# -_-V2.net
KiCad netlist of a schematic drawn in Altium Designer
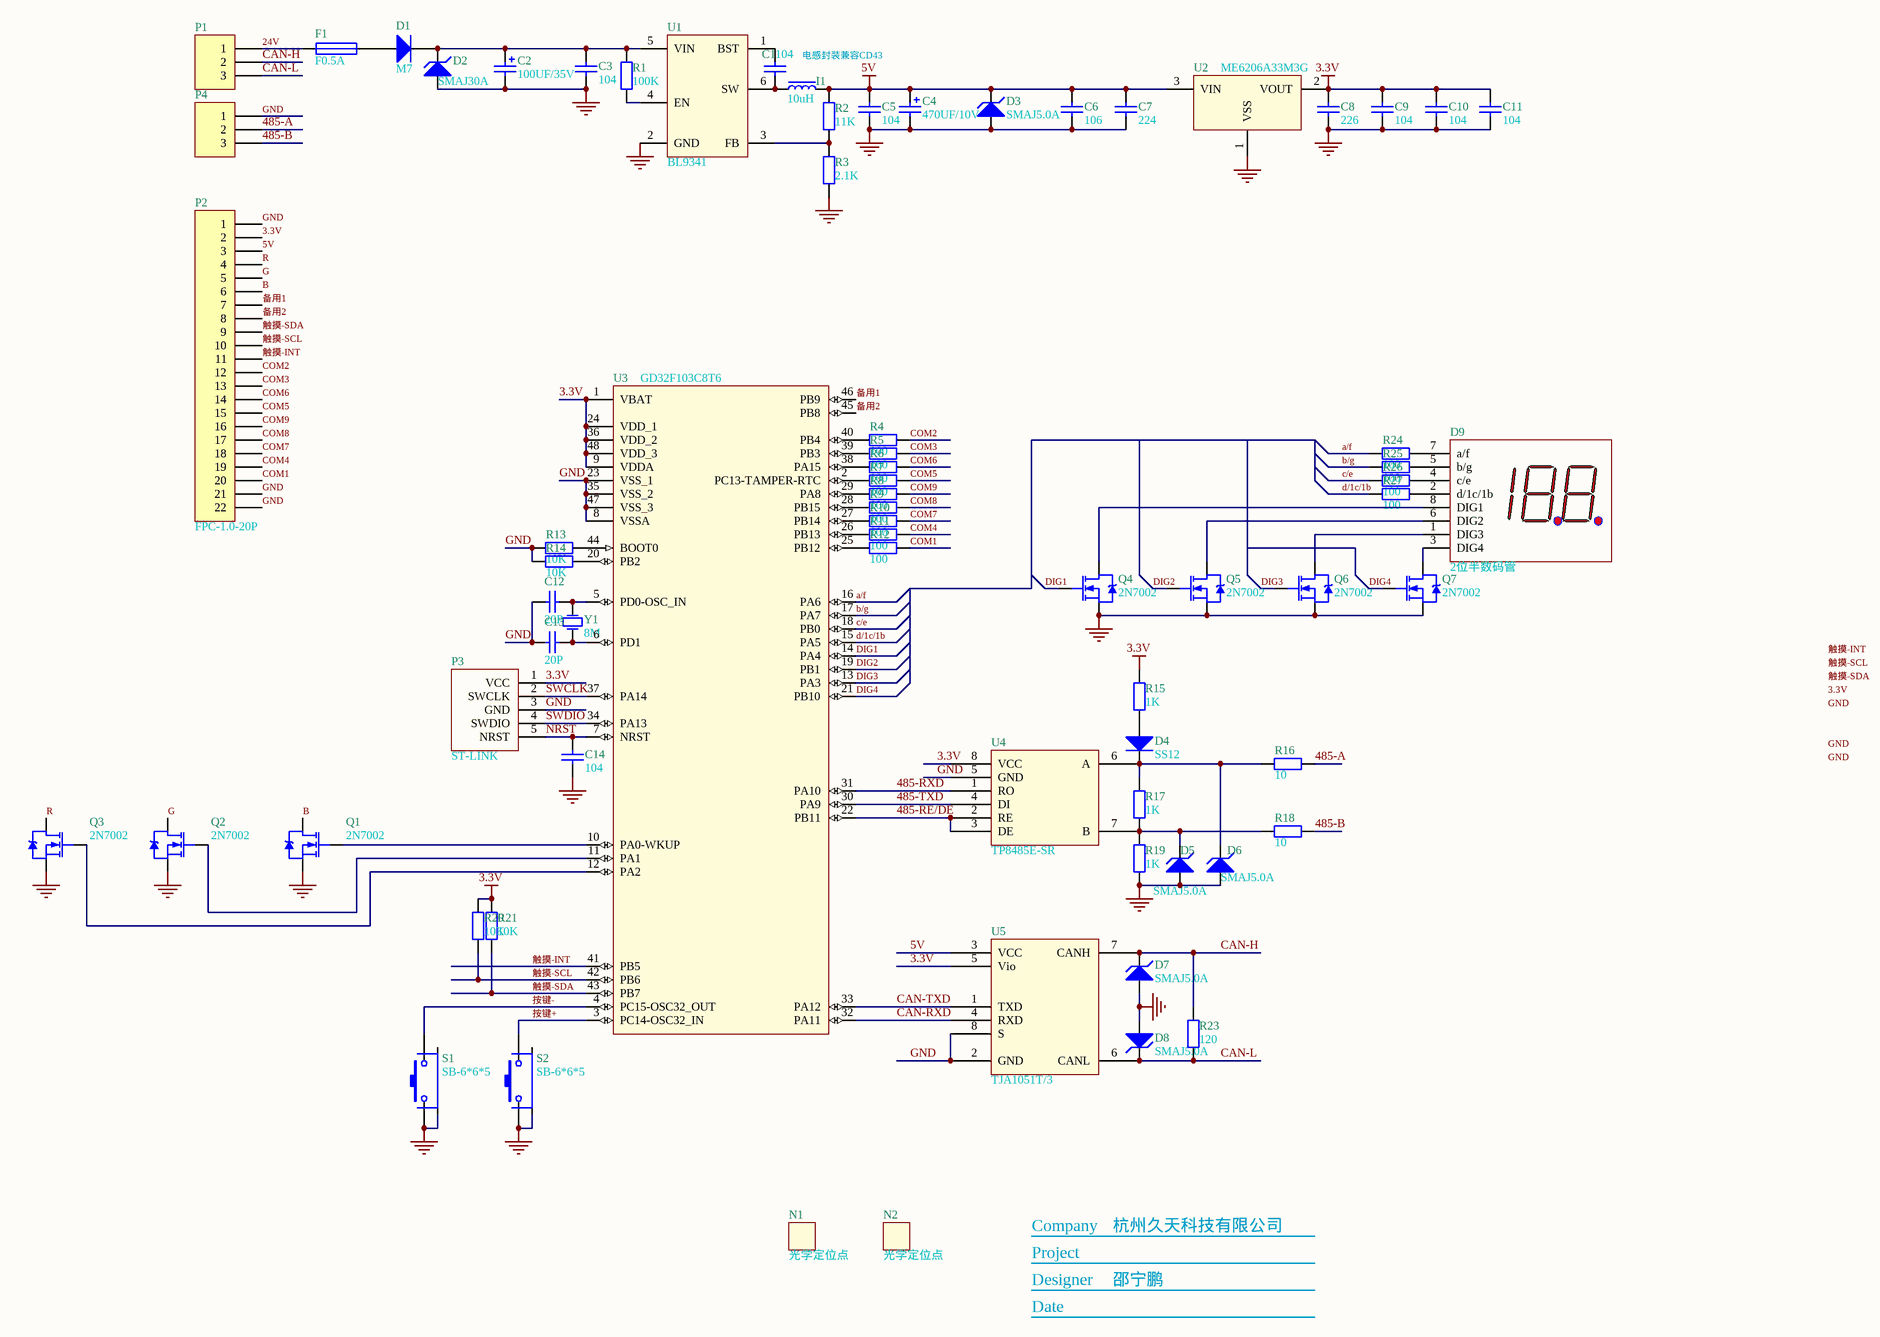
[diagram p0: 九键触摸面板-控制板-V2.SchDoc]

(export (version "E")
  (design (tool "Eeschema 10.0.6"))
  (components
    (comp (ref "C1")
      (value "104")
      (footprint "C-0603")
      (description "Capacitor")
      (fields (field (name "PUBLISHER") "Altium Limited"))
      (libsource (lib "元件2.0") (part "Cap"))
    )
    (comp (ref "C2")
      (value "100UF/35V")
      (footprint "贴片固态电容6.3*7.7")
      (description "Polarized Capacitor (Radial)")
      (fields (field (name "PUBLISHER") "Altium Limited"))
      (libsource (lib "元件2.0") (part "Cap Pol1"))
    )
    (comp (ref "C3")
      (value "104")
      (footprint "C-0603")
      (description "Capacitor")
      (fields (field (name "PUBLISHER") "Altium Limited"))
      (libsource (lib "元件2.0") (part "Cap"))
    )
    (comp (ref "C4")
      (value "470UF/10V")
      (footprint "贴片固态电容6.3*7.7")
      (description "Polarized Capacitor (Radial)")
      (fields (field (name "PUBLISHER") "Altium Limited"))
      (libsource (lib "元件2.0") (part "Cap Pol1"))
    )
    (comp (ref "C5")
      (value "104")
      (footprint "C-0603")
      (description "Capacitor")
      (fields (field (name "PUBLISHER") "Altium Limited"))
      (libsource (lib "元件2.0") (part "Cap"))
    )
    (comp (ref "C6")
      (value "106")
      (footprint "C-0603")
      (description "Capacitor")
      (fields (field (name "PUBLISHER") "Altium Limited"))
      (libsource (lib "元件2.0") (part "Cap"))
    )
    (comp (ref "C7")
      (value "224")
      (footprint "C-0603")
      (description "Capacitor")
      (fields (field (name "PUBLISHER") "Altium Limited"))
      (libsource (lib "元件2.0") (part "Cap"))
    )
    (comp (ref "C8")
      (value "226")
      (footprint "C-0603")
      (description "Capacitor")
      (fields (field (name "PUBLISHER") "Altium Limited"))
      (libsource (lib "元件2.0") (part "Cap"))
    )
    (comp (ref "C9")
      (value "104")
      (footprint "C-0603")
      (description "Capacitor")
      (fields (field (name "PUBLISHER") "Altium Limited"))
      (libsource (lib "元件2.0") (part "Cap"))
    )
    (comp (ref "C10")
      (value "104")
      (footprint "C-0603")
      (description "Capacitor")
      (fields (field (name "PUBLISHER") "Altium Limited"))
      (libsource (lib "元件2.0") (part "Cap"))
    )
    (comp (ref "C11")
      (value "104")
      (footprint "C-0603")
      (description "Capacitor")
      (fields (field (name "PUBLISHER") "Altium Limited"))
      (libsource (lib "元件2.0") (part "Cap"))
    )
    (comp (ref "C12")
      (value "20P")
      (footprint "C-0603")
      (description "0805")
      (fields (field (name "PUBLISHER") "Altium Limited"))
      (libsource (lib "2电容-V1.0") (part "Cap-0603"))
    )
    (comp (ref "C13")
      (value "20P")
      (footprint "C-0603")
      (description "0805")
      (fields (field (name "PUBLISHER") "Altium Limited"))
      (libsource (lib "2电容-V1.0") (part "Cap-0603"))
    )
    (comp (ref "C14")
      (value "104")
      (footprint "C-0603")
      (description "0805")
      (fields (field (name "PUBLISHER") "Altium Limited"))
      (libsource (lib "2电容-V1.0") (part "Cap-0603"))
    )
    (comp (ref "D1")
      (value "M7")
      (footprint "SMA")
      (description "SMA")
      (fields (field (name "PUBLISHER") "Altium Limited"))
      (libsource (lib "4二极管-V1.1") (part "M7"))
    )
    (comp (ref "D2")
      (value "SMAJ30A")
      (footprint "SMA")
      (description "SMB")
      (libsource (lib "4二极管-V1.1") (part "TVS-1"))
    )
    (comp (ref "D3")
      (value "SMAJ5.0A")
      (footprint "SMA")
      (description "SMB")
      (libsource (lib "4二极管-V1.1") (part "TVS-1"))
    )
    (comp (ref "D4")
      (value "SS12")
      (footprint "SOD-323/0805")
      (description "SMA")
      (libsource (lib "4二极管-V1.1") (part "SS14"))
    )
    (comp (ref "D5")
      (value "SMAJ5.0A")
      (footprint "SMA")
      (description "SMB")
      (libsource (lib "4二极管-V1.1") (part "TVS-1"))
    )
    (comp (ref "D6")
      (value "SMAJ5.0A")
      (footprint "SMA")
      (description "SMB")
      (libsource (lib "4二极管-V1.1") (part "TVS-1"))
    )
    (comp (ref "D7")
      (value "SMAJ5.0A")
      (footprint "SMA")
      (description "SMB")
      (libsource (lib "4二极管-V1.1") (part "TVS-1"))
    )
    (comp (ref "D8")
      (value "SMAJ5.0A")
      (footprint "SMA")
      (description "SMB")
      (libsource (lib "4二极管-V1.1") (part "TVS-1"))
    )
    (comp (ref "D9") (value "2位半数码管") (footprint "2位半0.25英寸") (libsource (lib "7显示屏-V1.0") (part "2位半数码管")))
    (comp (ref "F1")
      (value "F0.5A")
      (footprint "FUSE-3*10带引线")
      (description "Fuse")
      (fields (field (name "PUBLISHER") "Altium Limited"))
      (libsource (lib "11其他元件-V1.0") (part "Fuse 1"))
    )
    (comp (ref "I1") (value "10uH") (footprint "4030") (libsource (lib "3电感-V1.0") (part "Inductance3")))
    (comp (ref "N1") (value "光学定位点") (footprint "MARK-1mm-3mm") (libsource (lib "11其他元件-V1.0") (part "无引脚")))
    (comp (ref "N2") (value "光学定位点") (footprint "MARK-1mm-3mm") (libsource (lib "11其他元件-V1.0") (part "无引脚")))
    (comp (ref "P1")
      (value "~")
      (footprint "KF128-3P")
      (description "Header, 3-Pin")
      (fields (field (name "PUBLISHER") "Altium Limited"))
      (libsource (lib "5排针-V1.0") (part "Header 3"))
    )
    (comp (ref "P2")
      (value "FPC-1.0-20P")
      (footprint "FPC-1.0mm_20P下接翻盖")
      (description "Header, 22-Pin")
      (fields (field (name "PUBLISHER") "Altium Limited"))
      (libsource (lib "5排针-V1.0") (part "Header 22"))
    )
    (comp (ref "P3") (value "ST-LINK") (footprint "5P下载口") (libsource (lib "下载口") (part "ST-LINK-STM32")))
    (comp (ref "P4")
      (value "~")
      (footprint "KF128-3P")
      (description "Header, 3-Pin")
      (fields (field (name "PUBLISHER") "Altium Limited"))
      (libsource (lib "5排针-V1.0") (part "Header 3"))
    )
    (comp (ref "Q1") (value "2N7002") (footprint "SOT-23") (libsource (lib "4二极管-V1.1") (part "2N7002")))
    (comp (ref "Q2") (value "2N7002") (footprint "SOT-23") (libsource (lib "4二极管-V1.1") (part "2N7002")))
    (comp (ref "Q3") (value "2N7002") (footprint "SOT-23") (libsource (lib "4二极管-V1.1") (part "2N7002")))
    (comp (ref "Q4") (value "2N7002") (footprint "SOT-23") (libsource (lib "4二极管-V1.1") (part "2N7002")))
    (comp (ref "Q5") (value "2N7002") (footprint "SOT-23") (libsource (lib "4二极管-V1.1") (part "2N7002")))
    (comp (ref "Q6") (value "2N7002") (footprint "SOT-23") (libsource (lib "4二极管-V1.1") (part "2N7002")))
    (comp (ref "Q7") (value "2N7002") (footprint "SOT-23") (libsource (lib "4二极管-V1.1") (part "2N7002")))
    (comp (ref "R1")
      (value "100K")
      (footprint "R-0603")
      (description "0603")
      (fields (field (name "PUBLISHER") "Altium Limited"))
      (libsource (lib "1电阻-V1.0") (part "Res2-0603"))
    )
    (comp (ref "R2")
      (value "11K")
      (footprint "R-0603")
      (description "0603")
      (fields (field (name "PUBLISHER") "Altium Limited"))
      (libsource (lib "1电阻-V1.0") (part "Res2-0603"))
    )
    (comp (ref "R3")
      (value "2.1K")
      (footprint "R-0603")
      (description "0603")
      (fields (field (name "PUBLISHER") "Altium Limited"))
      (libsource (lib "1电阻-V1.0") (part "Res2-0603"))
    )
    (comp (ref "R4")
      (value "100")
      (footprint "R-0603")
      (description "0603")
      (fields (field (name "PUBLISHER") "Altium Limited"))
      (libsource (lib "") (part "Res2-0603_1"))
    )
    (comp (ref "R5")
      (value "100")
      (footprint "R-0603")
      (description "0603")
      (fields (field (name "PUBLISHER") "Altium Limited"))
      (libsource (lib "") (part "Res2-0603_1"))
    )
    (comp (ref "R6")
      (value "100")
      (footprint "R-0603")
      (description "0603")
      (fields (field (name "PUBLISHER") "Altium Limited"))
      (libsource (lib "") (part "Res2-0603_1"))
    )
    (comp (ref "R7")
      (value "100")
      (footprint "R-0603")
      (description "0603")
      (fields (field (name "PUBLISHER") "Altium Limited"))
      (libsource (lib "") (part "Res2-0603_1"))
    )
    (comp (ref "R8")
      (value "100")
      (footprint "R-0603")
      (description "0603")
      (fields (field (name "PUBLISHER") "Altium Limited"))
      (libsource (lib "") (part "Res2-0603_1"))
    )
    (comp (ref "R9")
      (value "100")
      (footprint "R-0603")
      (description "0603")
      (fields (field (name "PUBLISHER") "Altium Limited"))
      (libsource (lib "") (part "Res2-0603_1"))
    )
    (comp (ref "R10")
      (value "100")
      (footprint "R-0603")
      (description "0603")
      (fields (field (name "PUBLISHER") "Altium Limited"))
      (libsource (lib "") (part "Res2-0603_1"))
    )
    (comp (ref "R11")
      (value "100")
      (footprint "R-0603")
      (description "0603")
      (fields (field (name "PUBLISHER") "Altium Limited"))
      (libsource (lib "") (part "Res2-0603_1"))
    )
    (comp (ref "R12")
      (value "100")
      (footprint "R-0603")
      (description "0603")
      (fields (field (name "PUBLISHER") "Altium Limited"))
      (libsource (lib "") (part "Res2-0603_1"))
    )
    (comp (ref "R13")
      (value "10K")
      (footprint "R-0603")
      (description "0603")
      (fields (field (name "PUBLISHER") "Altium Limited"))
      (libsource (lib "1电阻-V1.0") (part "Res2-0603"))
    )
    (comp (ref "R14")
      (value "10K")
      (footprint "R-0603")
      (description "0603")
      (fields (field (name "PUBLISHER") "Altium Limited"))
      (libsource (lib "1电阻-V1.0") (part "Res2-0603"))
    )
    (comp (ref "R15")
      (value "1K")
      (footprint "R-0603")
      (description "Resistor")
      (fields (field (name "PUBLISHER") "Altium Limited"))
      (libsource (lib "元件2.0") (part "Res2"))
    )
    (comp (ref "R16")
      (value "10")
      (footprint "R-0603")
      (description "Resistor")
      (fields (field (name "PUBLISHER") "Altium Limited"))
      (libsource (lib "Miscellaneous Devices") (part "Res2"))
    )
    (comp (ref "R17")
      (value "1K")
      (footprint "R-1206")
      (description "Resistor")
      (fields (field (name "PUBLISHER") "Altium Limited"))
      (libsource (lib "") (part "Res2_1"))
    )
    (comp (ref "R18")
      (value "10")
      (footprint "R-0603")
      (description "Resistor")
      (fields (field (name "PUBLISHER") "Altium Limited"))
      (libsource (lib "Miscellaneous Devices") (part "Res2"))
    )
    (comp (ref "R19")
      (value "1K")
      (footprint "R-0603")
      (description "Resistor")
      (fields (field (name "PUBLISHER") "Altium Limited"))
      (libsource (lib "") (part "Res2_1"))
    )
    (comp (ref "R20")
      (value "10K")
      (footprint "R-0603")
      (description "0603")
      (fields (field (name "PUBLISHER") "Altium Limited"))
      (libsource (lib "") (part "Res2-0603_1"))
    )
    (comp (ref "R21")
      (value "10K")
      (footprint "R-0603")
      (description "0603")
      (fields (field (name "PUBLISHER") "Altium Limited"))
      (libsource (lib "") (part "Res2-0603_1"))
    )
    (comp (ref "R23")
      (value "120")
      (footprint "R-1206")
      (description "Resistor")
      (fields (field (name "PUBLISHER") "Altium Limited"))
      (libsource (lib "") (part "Res2_1"))
    )
    (comp (ref "R24")
      (value "100")
      (footprint "R-0603")
      (description "0603")
      (fields (field (name "PUBLISHER") "Altium Limited"))
      (libsource (lib "") (part "Res2-0603_1"))
    )
    (comp (ref "R25")
      (value "100")
      (footprint "R-0603")
      (description "0603")
      (fields (field (name "PUBLISHER") "Altium Limited"))
      (libsource (lib "") (part "Res2-0603_1"))
    )
    (comp (ref "R26")
      (value "100")
      (footprint "R-0603")
      (description "0603")
      (fields (field (name "PUBLISHER") "Altium Limited"))
      (libsource (lib "") (part "Res2-0603_1"))
    )
    (comp (ref "R27")
      (value "100")
      (footprint "R-0603")
      (description "0603")
      (fields (field (name "PUBLISHER") "Altium Limited"))
      (libsource (lib "") (part "Res2-0603_1"))
    )
    (comp (ref "S1")
      (value "SB-6*6*5")
      (footprint "SB-3*6*3.5")
      (fields (field (name "PUBLISHER") "Altium Limited"))
      (libsource (lib "开关-V1") (part "SB-6*6*5"))
    )
    (comp (ref "S2")
      (value "SB-6*6*5")
      (footprint "SB-3*6*3.5")
      (fields (field (name "PUBLISHER") "Altium Limited"))
      (libsource (lib "开关-V1") (part "SB-6*6*5"))
    )
    (comp (ref "U1") (value "BL9341") (footprint "SOT-23-6-m") (libsource (lib "电源芯片DC-DC") (part "BL9341")))
    (comp (ref "U2")
      (value "ME6206A33M3G")
      (footprint "SOT-23")
      (description "LDO稳压 SOT-23")
      (libsource (lib "电源芯片-线性稳压-V1") (part "ME6206A33M3G"))
    )
    (comp (ref "U3")
      (value "GD32F103C8T6")
      (footprint "LQFP48-L")
      (libsource (lib "9单片机-V1.0") (part "GD32F103C8T6"))
    )
    (comp (ref "U4")
      (value "TP8485E-SR")
      (footprint "SOP-8-m")
      (description "RS485总线转串口")
      (libsource (lib "集成电路1.0") (part "MAX3082"))
    )
    (comp (ref "U5") (value "TJA1051T/3") (footprint "SOP-8-M") (libsource (lib "通讯-V1") (part "TJA1051T/3")))
    (comp (ref "Y1") (value "8M") (footprint "HC-49SMD") (libsource (lib "11其他元件-V1.0") (part "晶振")))
  )
  (nets
    (net (code "1") (name "/24V") (class "Default")
      (node (ref "F1") (pin "1") (pinfunction "1_1") (pintype "passive"))
      (node (ref "P1") (pin "1") (pinfunction "1_1") (pintype "passive"))
    )
    (net (code "2") (name "/485-A") (class "Default")
      (node (ref "P4") (pin "2") (pinfunction "2_2") (pintype "passive"))
      (node (ref "R16") (pin "1") (pinfunction "1_1") (pintype "passive"))
    )
    (net (code "3") (name "/485-B") (class "Default")
      (node (ref "P4") (pin "3") (pinfunction "3_3") (pintype "passive"))
      (node (ref "R18") (pin "1") (pinfunction "1_1") (pintype "passive"))
    )
    (net (code "4") (name "/485-RE{slash}DE") (class "Default")
      (node (ref "U3") (pin "22") (pinfunction "PB11_22") (pintype "bidirectional"))
      (node (ref "U4") (pin "2") (pinfunction "RE_2") (pintype "passive"))
      (node (ref "U4") (pin "3") (pinfunction "DE_3") (pintype "passive"))
    )
    (net (code "5") (name "/485-RXD") (class "Default")
      (node (ref "U3") (pin "31") (pinfunction "PA10_31") (pintype "bidirectional"))
      (node (ref "U4") (pin "1") (pinfunction "RO_1") (pintype "passive"))
    )
    (net (code "6") (name "/485-TXD") (class "Default")
      (node (ref "U3") (pin "30") (pinfunction "PA9_30") (pintype "bidirectional"))
      (node (ref "U4") (pin "4") (pinfunction "DI_4") (pintype "passive"))
    )
    (net (code "7") (name "/B") (class "Default")
      (node (ref "P2") (pin "6") (pinfunction "6_6") (pintype "passive"))
      (node (ref "Q1") (pin "3") (pinfunction "D_3") (pintype "passive"))
    )
    (net (code "8") (name "/CAN-H") (class "Default")
      (node (ref "D7") (pin "2") (pinfunction "K_2") (pintype "passive"))
      (node (ref "P1") (pin "2") (pinfunction "2_2") (pintype "passive"))
      (node (ref "R23") (pin "1") (pinfunction "1_1") (pintype "passive"))
      (node (ref "U5") (pin "7") (pinfunction "CANH_7") (pintype "passive"))
    )
    (net (code "9") (name "/CAN-L") (class "Default")
      (node (ref "D8") (pin "2") (pinfunction "K_2") (pintype "passive"))
      (node (ref "P1") (pin "3") (pinfunction "3_3") (pintype "passive"))
      (node (ref "R23") (pin "2") (pinfunction "2_2") (pintype "passive"))
      (node (ref "U5") (pin "6") (pinfunction "CANL_6") (pintype "passive"))
    )
    (net (code "10") (name "/CAN-RXD") (class "Default")
      (node (ref "U3") (pin "32") (pinfunction "PA11_32") (pintype "bidirectional"))
      (node (ref "U5") (pin "4") (pinfunction "RXD_4") (pintype "passive"))
    )
    (net (code "11") (name "/CAN-TXD") (class "Default")
      (node (ref "U3") (pin "33") (pinfunction "PA12_33") (pintype "bidirectional"))
      (node (ref "U5") (pin "1") (pinfunction "TXD_1") (pintype "passive"))
    )
    (net (code "12") (name "/COM1") (class "Default")
      (node (ref "P2") (pin "20") (pinfunction "20_20") (pintype "passive"))
      (node (ref "R12") (pin "2") (pinfunction "2_2") (pintype "passive"))
    )
    (net (code "13") (name "/COM2") (class "Default")
      (node (ref "P2") (pin "12") (pinfunction "12_12") (pintype "passive"))
      (node (ref "R4") (pin "2") (pinfunction "2_2") (pintype "passive"))
    )
    (net (code "14") (name "/COM3") (class "Default")
      (node (ref "P2") (pin "13") (pinfunction "13_13") (pintype "passive"))
      (node (ref "R5") (pin "2") (pinfunction "2_2") (pintype "passive"))
    )
    (net (code "15") (name "/COM4") (class "Default")
      (node (ref "P2") (pin "19") (pinfunction "19_19") (pintype "passive"))
      (node (ref "R11") (pin "2") (pinfunction "2_2") (pintype "passive"))
    )
    (net (code "16") (name "/COM5") (class "Default")
      (node (ref "P2") (pin "15") (pinfunction "15_15") (pintype "passive"))
      (node (ref "R7") (pin "2") (pinfunction "2_2") (pintype "passive"))
    )
    (net (code "17") (name "/COM6") (class "Default")
      (node (ref "P2") (pin "14") (pinfunction "14_14") (pintype "passive"))
      (node (ref "R6") (pin "2") (pinfunction "2_2") (pintype "passive"))
    )
    (net (code "18") (name "/COM7") (class "Default")
      (node (ref "P2") (pin "18") (pinfunction "18_18") (pintype "passive"))
      (node (ref "R10") (pin "2") (pinfunction "2_2") (pintype "passive"))
    )
    (net (code "19") (name "/COM8") (class "Default")
      (node (ref "P2") (pin "17") (pinfunction "17_17") (pintype "passive"))
      (node (ref "R9") (pin "2") (pinfunction "2_2") (pintype "passive"))
    )
    (net (code "20") (name "/COM9") (class "Default")
      (node (ref "P2") (pin "16") (pinfunction "16_16") (pintype "passive"))
      (node (ref "R8") (pin "2") (pinfunction "2_2") (pintype "passive"))
    )
    (net (code "21") (name "/DIG1") (class "Default")
      (node (ref "Q4") (pin "1") (pinfunction "G_1") (pintype "passive"))
      (node (ref "U3") (pin "14") (pinfunction "PA4_14") (pintype "bidirectional"))
    )
    (net (code "22") (name "/DIG2") (class "Default")
      (node (ref "Q5") (pin "1") (pinfunction "G_1") (pintype "passive"))
      (node (ref "U3") (pin "19") (pinfunction "PB1_19") (pintype "bidirectional"))
    )
    (net (code "23") (name "/DIG3") (class "Default")
      (node (ref "Q6") (pin "1") (pinfunction "G_1") (pintype "passive"))
      (node (ref "U3") (pin "13") (pinfunction "PA3_13") (pintype "bidirectional"))
    )
    (net (code "24") (name "/DIG4") (class "Default")
      (node (ref "Q7") (pin "1") (pinfunction "G_1") (pintype "passive"))
      (node (ref "U3") (pin "21") (pinfunction "PB10_21") (pintype "bidirectional"))
    )
    (net (code "25") (name "/G") (class "Default")
      (node (ref "P2") (pin "5") (pinfunction "5_5") (pintype "passive"))
      (node (ref "Q2") (pin "3") (pinfunction "D_3") (pintype "passive"))
    )
    (net (code "26") (name "/NRST") (class "Default")
      (node (ref "C14") (pin "2") (pinfunction "2_2") (pintype "passive"))
      (node (ref "P3") (pin "5") (pinfunction "NRST_5") (pintype "passive"))
      (node (ref "U3") (pin "7") (pinfunction "NRST_7") (pintype "bidirectional"))
    )
    (net (code "27") (name "/R") (class "Default")
      (node (ref "P2") (pin "4") (pinfunction "4_4") (pintype "passive"))
      (node (ref "Q3") (pin "3") (pinfunction "D_3") (pintype "passive"))
    )
    (net (code "28") (name "/SWCLK") (class "Default")
      (node (ref "P3") (pin "2") (pinfunction "SWCLK_2") (pintype "passive"))
      (node (ref "U3") (pin "37") (pinfunction "PA14_37") (pintype "bidirectional"))
    )
    (net (code "29") (name "/SWDIO") (class "Default")
      (node (ref "P3") (pin "4") (pinfunction "SWDIO_4") (pintype "passive"))
      (node (ref "U3") (pin "34") (pinfunction "PA13_34") (pintype "bidirectional"))
    )
    (net (code "30") (name "/a{slash}f") (class "Default")
      (node (ref "R24") (pin "1") (pinfunction "1_1") (pintype "passive"))
      (node (ref "U3") (pin "16") (pinfunction "PA6_16") (pintype "bidirectional"))
    )
    (net (code "31") (name "/b{slash}g") (class "Default")
      (node (ref "R25") (pin "1") (pinfunction "1_1") (pintype "passive"))
      (node (ref "U3") (pin "17") (pinfunction "PA7_17") (pintype "bidirectional"))
    )
    (net (code "32") (name "/c{slash}e") (class "Default")
      (node (ref "R26") (pin "1") (pinfunction "1_1") (pintype "passive"))
      (node (ref "U3") (pin "18") (pinfunction "PB0_18") (pintype "bidirectional"))
    )
    (net (code "33") (name "/d{slash}1c{slash}1b") (class "Default")
      (node (ref "R27") (pin "1") (pinfunction "1_1") (pintype "passive"))
      (node (ref "U3") (pin "15") (pinfunction "PA5_15") (pintype "bidirectional"))
    )
    (net (code "34") (name "/备用1") (class "Default")
      (node (ref "P2") (pin "7") (pinfunction "7_7") (pintype "passive"))
      (node (ref "U3") (pin "46") (pinfunction "PB9_46") (pintype "bidirectional"))
    )
    (net (code "35") (name "/备用2") (class "Default")
      (node (ref "P2") (pin "8") (pinfunction "8_8") (pintype "passive"))
      (node (ref "U3") (pin "45") (pinfunction "PB8_45") (pintype "bidirectional"))
    )
    (net (code "36") (name "/按键+") (class "Default")
      (node (ref "S2") (pin "1") (pinfunction "1_1") (pintype "passive"))
      (node (ref "U3") (pin "3") (pinfunction "PC14-OSC32_IN_3") (pintype "bidirectional"))
    )
    (net (code "37") (name "/按键-") (class "Default")
      (node (ref "S1") (pin "1") (pinfunction "1_1") (pintype "passive"))
      (node (ref "U3") (pin "4") (pinfunction "PC15-OSC32_OUT_4") (pintype "bidirectional"))
    )
    (net (code "38") (name "/触摸-INT") (class "Default")
      (node (ref "P2") (pin "11") (pinfunction "11_11") (pintype "passive"))
      (node (ref "U3") (pin "41") (pinfunction "PB5_41") (pintype "bidirectional"))
    )
    (net (code "39") (name "/触摸-SCL") (class "Default")
      (node (ref "P2") (pin "10") (pinfunction "10_10") (pintype "passive"))
      (node (ref "R20") (pin "1") (pinfunction "1_1") (pintype "passive"))
      (node (ref "U3") (pin "42") (pinfunction "PB6_42") (pintype "bidirectional"))
    )
    (net (code "40") (name "/触摸-SDA") (class "Default")
      (node (ref "P2") (pin "9") (pinfunction "9_9") (pintype "passive"))
      (node (ref "R21") (pin "1") (pinfunction "1_1") (pintype "passive"))
      (node (ref "U3") (pin "43") (pinfunction "PB7_43") (pintype "bidirectional"))
    )
    (net (code "41") (name "3.3V") (class "Default")
      (node (ref "C10") (pin "2") (pinfunction "2_2") (pintype "passive"))
      (node (ref "C11") (pin "2") (pinfunction "2_2") (pintype "passive"))
      (node (ref "C8") (pin "2") (pinfunction "2_2") (pintype "passive"))
      (node (ref "C9") (pin "2") (pinfunction "2_2") (pintype "passive"))
      (node (ref "P2") (pin "2") (pinfunction "2_2") (pintype "passive"))
      (node (ref "P3") (pin "1") (pinfunction "VCC_1") (pintype "passive"))
      (node (ref "R15") (pin "1") (pinfunction "1_1") (pintype "passive"))
      (node (ref "R20") (pin "2") (pinfunction "2_2") (pintype "passive"))
      (node (ref "R21") (pin "2") (pinfunction "2_2") (pintype "passive"))
      (node (ref "U2") (pin "2") (pinfunction "VOUT_2") (pintype "passive"))
      (node (ref "U3") (pin "1") (pinfunction "VBAT_1") (pintype "power_in"))
      (node (ref "U3") (pin "24") (pinfunction "VDD_1_24") (pintype "power_in"))
      (node (ref "U3") (pin "36") (pinfunction "VDD_2_36") (pintype "power_in"))
      (node (ref "U3") (pin "48") (pinfunction "VDD_3_48") (pintype "power_in"))
      (node (ref "U3") (pin "9") (pinfunction "VDDA_9") (pintype "power_in"))
      (node (ref "U4") (pin "8") (pinfunction "VCC_8") (pintype "passive"))
      (node (ref "U5") (pin "5") (pinfunction "Vio_5") (pintype "passive"))
    )
    (net (code "42") (name "5V") (class "Default")
      (node (ref "C4") (pin "1") (pinfunction "1_1") (pintype "passive"))
      (node (ref "C5") (pin "2") (pinfunction "2_2") (pintype "passive"))
      (node (ref "C6") (pin "2") (pinfunction "2_2") (pintype "passive"))
      (node (ref "C7") (pin "2") (pinfunction "2_2") (pintype "passive"))
      (node (ref "D3") (pin "2") (pinfunction "K_2") (pintype "passive"))
      (node (ref "I1") (pin "2") (pinfunction "2_2") (pintype "passive"))
      (node (ref "P2") (pin "3") (pinfunction "3_3") (pintype "passive"))
      (node (ref "R2") (pin "1") (pinfunction "1_1") (pintype "passive"))
      (node (ref "U2") (pin "3") (pinfunction "VIN_3") (pintype "passive"))
      (node (ref "U5") (pin "3") (pinfunction "VCC_3") (pintype "passive"))
    )
    (net (code "43") (name "GND") (class "Default")
      (node (ref "C10") (pin "1") (pinfunction "1_1") (pintype "passive"))
      (node (ref "C11") (pin "1") (pinfunction "1_1") (pintype "passive"))
      (node (ref "C12") (pin "1") (pinfunction "1_1") (pintype "passive"))
      (node (ref "C13") (pin "1") (pinfunction "1_1") (pintype "passive"))
      (node (ref "C14") (pin "1") (pinfunction "1_1") (pintype "passive"))
      (node (ref "C2") (pin "2") (pinfunction "2_2") (pintype "passive"))
      (node (ref "C3") (pin "1") (pinfunction "1_1") (pintype "passive"))
      (node (ref "C4") (pin "2") (pinfunction "2_2") (pintype "passive"))
      (node (ref "C5") (pin "1") (pinfunction "1_1") (pintype "passive"))
      (node (ref "C6") (pin "1") (pinfunction "1_1") (pintype "passive"))
      (node (ref "C7") (pin "1") (pinfunction "1_1") (pintype "passive"))
      (node (ref "C8") (pin "1") (pinfunction "1_1") (pintype "passive"))
      (node (ref "C9") (pin "1") (pinfunction "1_1") (pintype "passive"))
      (node (ref "D2") (pin "1") (pinfunction "A_1") (pintype "passive"))
      (node (ref "D3") (pin "1") (pinfunction "A_1") (pintype "passive"))
      (node (ref "D5") (pin "1") (pinfunction "A_1") (pintype "passive"))
      (node (ref "D6") (pin "1") (pinfunction "A_1") (pintype "passive"))
      (node (ref "D7") (pin "1") (pinfunction "A_1") (pintype "passive"))
      (node (ref "D8") (pin "1") (pinfunction "A_1") (pintype "passive"))
      (node (ref "P2") (pin "1") (pinfunction "1_1") (pintype "passive"))
      (node (ref "P2") (pin "21") (pinfunction "21_21") (pintype "passive"))
      (node (ref "P2") (pin "22") (pinfunction "22_22") (pintype "passive"))
      (node (ref "P3") (pin "3") (pinfunction "GND_3") (pintype "passive"))
      (node (ref "P4") (pin "1") (pinfunction "1_1") (pintype "passive"))
      (node (ref "Q1") (pin "2") (pinfunction "S_2") (pintype "passive"))
      (node (ref "Q2") (pin "2") (pinfunction "S_2") (pintype "passive"))
      (node (ref "Q3") (pin "2") (pinfunction "S_2") (pintype "passive"))
      (node (ref "Q4") (pin "2") (pinfunction "S_2") (pintype "passive"))
      (node (ref "Q5") (pin "2") (pinfunction "S_2") (pintype "passive"))
      (node (ref "Q6") (pin "2") (pinfunction "S_2") (pintype "passive"))
      (node (ref "Q7") (pin "2") (pinfunction "S_2") (pintype "passive"))
      (node (ref "R13") (pin "2") (pinfunction "2_2") (pintype "passive"))
      (node (ref "R14") (pin "2") (pinfunction "2_2") (pintype "passive"))
      (node (ref "R19") (pin "1") (pinfunction "1_1") (pintype "passive"))
      (node (ref "R3") (pin "2") (pinfunction "2_2") (pintype "passive"))
      (node (ref "S1") (pin "2") (pinfunction "2_2") (pintype "passive"))
      (node (ref "S1") (pin "3") (pinfunction "3_3") (pintype "passive"))
      (node (ref "S2") (pin "2") (pinfunction "2_2") (pintype "passive"))
      (node (ref "S2") (pin "3") (pinfunction "3_3") (pintype "passive"))
      (node (ref "U1") (pin "2") (pinfunction "GND_2") (pintype "passive"))
      (node (ref "U2") (pin "1") (pinfunction "VSS_1") (pintype "passive"))
      (node (ref "U3") (pin "23") (pinfunction "VSS_1_23") (pintype "power_in"))
      (node (ref "U3") (pin "35") (pinfunction "VSS_2_35") (pintype "power_in"))
      (node (ref "U3") (pin "47") (pinfunction "VSS_3_47") (pintype "power_in"))
      (node (ref "U3") (pin "8") (pinfunction "VSSA_8") (pintype "power_in"))
      (node (ref "U4") (pin "5") (pinfunction "GND_5") (pintype "passive"))
      (node (ref "U5") (pin "2") (pinfunction "GND_2") (pintype "passive"))
      (node (ref "U5") (pin "8") (pinfunction "S_8") (pintype "passive"))
    )
    (net (code "44") (name "Net-(D1-A)") (class "Default")
      (node (ref "D1") (pin "1") (pinfunction "A_1") (pintype "passive"))
      (node (ref "F1") (pin "2") (pinfunction "2_2") (pintype "passive"))
    )
    (net (code "45") (name "Net-(D1-K)") (class "Default")
      (node (ref "C2") (pin "1") (pinfunction "1_1") (pintype "passive"))
      (node (ref "C3") (pin "2") (pinfunction "2_2") (pintype "passive"))
      (node (ref "D1") (pin "2") (pinfunction "K_2") (pintype "passive"))
      (node (ref "D2") (pin "2") (pinfunction "K_2") (pintype "passive"))
      (node (ref "R1") (pin "1") (pinfunction "1_1") (pintype "passive"))
      (node (ref "U1") (pin "5") (pinfunction "VIN_5") (pintype "passive"))
    )
    (net (code "46") (name "Net-(D4-A)") (class "Default")
      (node (ref "D4") (pin "1") (pinfunction "A_1") (pintype "passive"))
      (node (ref "R15") (pin "2") (pinfunction "2_2") (pintype "passive"))
    )
    (net (code "47") (name "Net-(D4-K)") (class "Default")
      (node (ref "D4") (pin "2") (pinfunction "K_2") (pintype "passive"))
      (node (ref "D6") (pin "2") (pinfunction "K_2") (pintype "passive"))
      (node (ref "R16") (pin "2") (pinfunction "2_2") (pintype "passive"))
      (node (ref "R17") (pin "1") (pinfunction "1_1") (pintype "passive"))
      (node (ref "U4") (pin "6") (pinfunction "A_6") (pintype "passive"))
    )
    (net (code "48") (name "Net-(D5-K)") (class "Default")
      (node (ref "D5") (pin "2") (pinfunction "K_2") (pintype "passive"))
      (node (ref "R17") (pin "2") (pinfunction "2_2") (pintype "passive"))
      (node (ref "R18") (pin "2") (pinfunction "2_2") (pintype "passive"))
      (node (ref "R19") (pin "2") (pinfunction "2_2") (pintype "passive"))
      (node (ref "U4") (pin "7") (pinfunction "B_7") (pintype "passive"))
    )
    (net (code "49") (name "Net-(D9-DIG1)") (class "Default")
      (node (ref "D9") (pin "8") (pinfunction "DIG1_8") (pintype "passive"))
      (node (ref "Q4") (pin "3") (pinfunction "D_3") (pintype "passive"))
    )
    (net (code "50") (name "Net-(D9-DIG2)") (class "Default")
      (node (ref "D9") (pin "6") (pinfunction "DIG2_6") (pintype "passive"))
      (node (ref "Q5") (pin "3") (pinfunction "D_3") (pintype "passive"))
    )
    (net (code "51") (name "Net-(D9-DIG3)") (class "Default")
      (node (ref "D9") (pin "1") (pinfunction "DIG3_1") (pintype "passive"))
      (node (ref "Q6") (pin "3") (pinfunction "D_3") (pintype "passive"))
    )
    (net (code "52") (name "Net-(D9-DIG4)") (class "Default")
      (node (ref "D9") (pin "3") (pinfunction "DIG4_3") (pintype "passive"))
      (node (ref "Q7") (pin "3") (pinfunction "D_3") (pintype "passive"))
    )
    (net (code "53") (name "Net-(D9-a{slash}f)") (class "Default")
      (node (ref "D9") (pin "7") (pinfunction "a/f_7") (pintype "passive"))
      (node (ref "R24") (pin "2") (pinfunction "2_2") (pintype "passive"))
    )
    (net (code "54") (name "Net-(D9-b{slash}g)") (class "Default")
      (node (ref "D9") (pin "5") (pinfunction "b/g_5") (pintype "passive"))
      (node (ref "R25") (pin "2") (pinfunction "2_2") (pintype "passive"))
    )
    (net (code "55") (name "Net-(D9-c{slash}e)") (class "Default")
      (node (ref "D9") (pin "4") (pinfunction "c/e_4") (pintype "passive"))
      (node (ref "R26") (pin "2") (pinfunction "2_2") (pintype "passive"))
    )
    (net (code "56") (name "Net-(D9-d{slash}1c{slash}1b)") (class "Default")
      (node (ref "D9") (pin "2") (pinfunction "d/1c/1b_2") (pintype "passive"))
      (node (ref "R27") (pin "2") (pinfunction "2_2") (pintype "passive"))
    )
    (net (code "57") (name "Net-(Q1-G)") (class "Default")
      (node (ref "Q1") (pin "1") (pinfunction "G_1") (pintype "passive"))
      (node (ref "U3") (pin "10") (pinfunction "PA0-WKUP_10") (pintype "bidirectional"))
    )
    (net (code "58") (name "Net-(Q2-G)") (class "Default")
      (node (ref "Q2") (pin "1") (pinfunction "G_1") (pintype "passive"))
      (node (ref "U3") (pin "11") (pinfunction "PA1_11") (pintype "bidirectional"))
    )
    (net (code "59") (name "Net-(Q3-G)") (class "Default")
      (node (ref "Q3") (pin "1") (pinfunction "G_1") (pintype "passive"))
      (node (ref "U3") (pin "12") (pinfunction "PA2_12") (pintype "bidirectional"))
    )
    (net (code "60") (name "Net-(U1-BST)") (class "Default")
      (node (ref "C1") (pin "2") (pinfunction "2_2") (pintype "passive"))
      (node (ref "U1") (pin "1") (pinfunction "BST_1") (pintype "passive"))
    )
    (net (code "61") (name "Net-(U1-EN)") (class "Default")
      (node (ref "R1") (pin "2") (pinfunction "2_2") (pintype "passive"))
      (node (ref "U1") (pin "4") (pinfunction "EN_4") (pintype "passive"))
    )
    (net (code "62") (name "Net-(U1-FB)") (class "Default")
      (node (ref "R2") (pin "2") (pinfunction "2_2") (pintype "passive"))
      (node (ref "R3") (pin "1") (pinfunction "1_1") (pintype "passive"))
      (node (ref "U1") (pin "3") (pinfunction "FB_3") (pintype "passive"))
    )
    (net (code "63") (name "Net-(U1-SW)") (class "Default")
      (node (ref "C1") (pin "1") (pinfunction "1_1") (pintype "passive"))
      (node (ref "I1") (pin "1") (pinfunction "1_1") (pintype "passive"))
      (node (ref "U1") (pin "6") (pinfunction "SW_6") (pintype "passive"))
    )
    (net (code "64") (name "Net-(U3-BOOT0)") (class "Default")
      (node (ref "R13") (pin "1") (pinfunction "1_1") (pintype "passive"))
      (node (ref "U3") (pin "44") (pinfunction "BOOT0_44") (pintype "input"))
    )
    (net (code "65") (name "Net-(U3-PA8)") (class "Default")
      (node (ref "R8") (pin "1") (pinfunction "1_1") (pintype "passive"))
      (node (ref "U3") (pin "29") (pinfunction "PA8_29") (pintype "bidirectional"))
    )
    (net (code "66") (name "Net-(U3-PA15)") (class "Default")
      (node (ref "R6") (pin "1") (pinfunction "1_1") (pintype "passive"))
      (node (ref "U3") (pin "38") (pinfunction "PA15_38") (pintype "bidirectional"))
    )
    (net (code "67") (name "Net-(U3-PB2)") (class "Default")
      (node (ref "R14") (pin "1") (pinfunction "1_1") (pintype "passive"))
      (node (ref "U3") (pin "20") (pinfunction "PB2_20") (pintype "bidirectional"))
    )
    (net (code "68") (name "Net-(U3-PB3)") (class "Default")
      (node (ref "R5") (pin "1") (pinfunction "1_1") (pintype "passive"))
      (node (ref "U3") (pin "39") (pinfunction "PB3_39") (pintype "bidirectional"))
    )
    (net (code "69") (name "Net-(U3-PB4)") (class "Default")
      (node (ref "R4") (pin "1") (pinfunction "1_1") (pintype "passive"))
      (node (ref "U3") (pin "40") (pinfunction "PB4_40") (pintype "bidirectional"))
    )
    (net (code "70") (name "Net-(U3-PB12)") (class "Default")
      (node (ref "R12") (pin "1") (pinfunction "1_1") (pintype "passive"))
      (node (ref "U3") (pin "25") (pinfunction "PB12_25") (pintype "bidirectional"))
    )
    (net (code "71") (name "Net-(U3-PB13)") (class "Default")
      (node (ref "R11") (pin "1") (pinfunction "1_1") (pintype "passive"))
      (node (ref "U3") (pin "26") (pinfunction "PB13_26") (pintype "bidirectional"))
    )
    (net (code "72") (name "Net-(U3-PB14)") (class "Default")
      (node (ref "R10") (pin "1") (pinfunction "1_1") (pintype "passive"))
      (node (ref "U3") (pin "27") (pinfunction "PB14_27") (pintype "bidirectional"))
    )
    (net (code "73") (name "Net-(U3-PB15)") (class "Default")
      (node (ref "R9") (pin "1") (pinfunction "1_1") (pintype "passive"))
      (node (ref "U3") (pin "28") (pinfunction "PB15_28") (pintype "bidirectional"))
    )
    (net (code "74") (name "Net-(U3-PC13-TAMPER-RTC)") (class "Default")
      (node (ref "R7") (pin "1") (pinfunction "1_1") (pintype "passive"))
      (node (ref "U3") (pin "2") (pinfunction "PC13-TAMPER-RTC_2") (pintype "bidirectional"))
    )
    (net (code "75") (name "Net-(U3-PD0-OSC_IN)") (class "Default")
      (node (ref "C12") (pin "2") (pinfunction "2_2") (pintype "passive"))
      (node (ref "U3") (pin "5") (pinfunction "PD0-OSC_IN_5") (pintype "bidirectional"))
      (node (ref "Y1") (pin "2") (pinfunction "OSC2_2") (pintype "passive"))
    )
    (net (code "76") (name "Net-(U3-PD1)") (class "Default")
      (node (ref "C13") (pin "2") (pinfunction "2_2") (pintype "passive"))
      (node (ref "U3") (pin "6") (pinfunction "PD1_6") (pintype "bidirectional"))
      (node (ref "Y1") (pin "1") (pinfunction "OSC1_1") (pintype "passive"))
    )
    (net (code "77") (name "unconnected-(S1-Pad3)") (class "Default")
      (node (ref "S1") (pin "3") (pinfunction "3_3") (pintype "passive"))
    )
    (net (code "78") (name "unconnected-(S2-Pad3)") (class "Default")
      (node (ref "S2") (pin "3") (pinfunction "3_3") (pintype "passive"))
    )
  )
)
